# 468332_001_Step-Down_Controller.net
KiCad netlist of a schematic drawn in Altium Designer
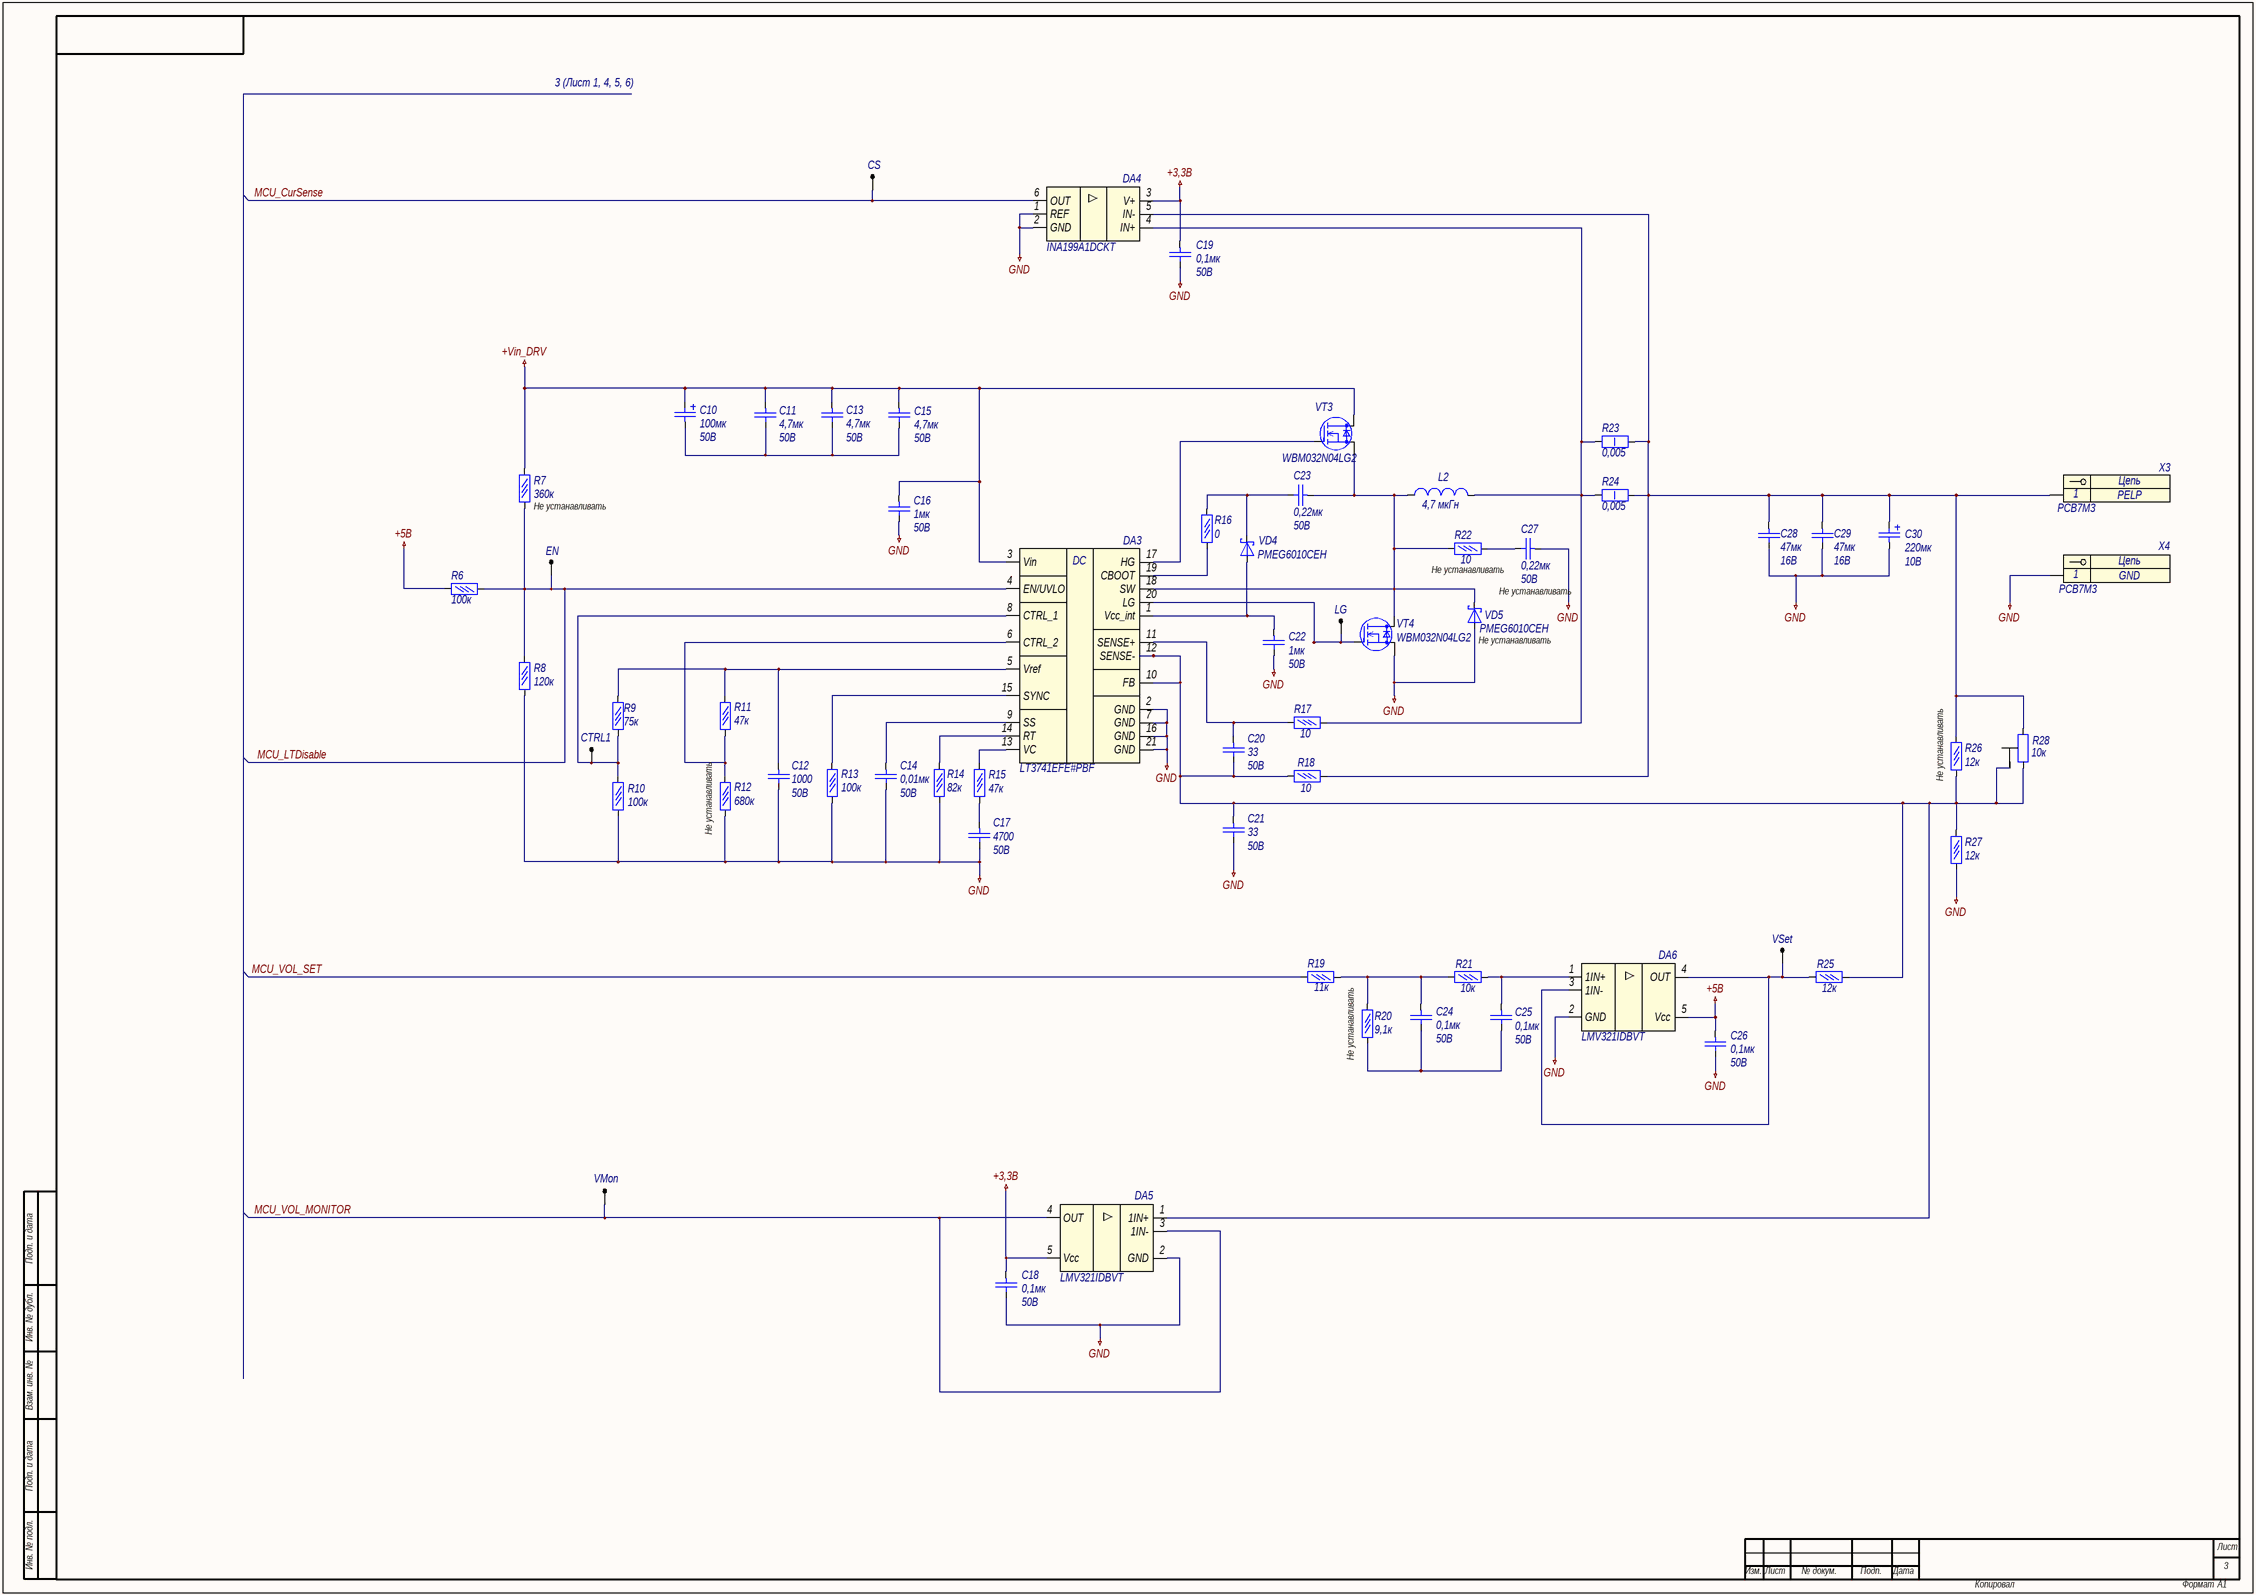
[diagram p0: РЕУН.468332.001_Step-Down_Controller.SchDoc]

(export (version "E")
  (design (tool "Eeschema 10.0.6"))
  (components
    (comp (ref "C10")
      (value "100мк")
      (footprint "C0805_AA")
      (description "Конденсатор пол.")
      (fields (field (name "VOLTAGE") "50В"))
      (libsource (lib "Library_Diana") (part "Конденсатор поляризованный"))
    )
    (comp (ref "C11")
      (value "4,7мк")
      (footprint "C0805_AA")
      (description "Конденсатор кер.")
      (fields (field (name "VOLTAGE") "50В"))
      (libsource (lib "Library_Diana") (part "Конденсатор кер."))
    )
    (comp (ref "C12")
      (value "1000")
      (footprint "C0805_AA")
      (description "Конденсатор кер.")
      (fields (field (name "VOLTAGE") "50В"))
      (libsource (lib "Library_Diana") (part "Конденсатор кер."))
    )
    (comp (ref "C13")
      (value "4,7мк")
      (footprint "C0805_AA")
      (description "Конденсатор кер.")
      (fields (field (name "VOLTAGE") "50В"))
      (libsource (lib "Library_Diana") (part "Конденсатор кер."))
    )
    (comp (ref "C14")
      (value "0,01мк")
      (footprint "C0805_AA")
      (description "Конденсатор кер.")
      (fields (field (name "VOLTAGE") "50В"))
      (libsource (lib "Library_Diana") (part "Конденсатор кер."))
    )
    (comp (ref "C15")
      (value "4,7мк")
      (footprint "C0805_AA")
      (description "Конденсатор кер.")
      (fields (field (name "VOLTAGE") "50В"))
      (libsource (lib "Library_Diana") (part "Конденсатор кер."))
    )
    (comp (ref "C16")
      (value "1мк")
      (footprint "C0805_AA")
      (description "Конденсатор кер.")
      (fields (field (name "VOLTAGE") "50В"))
      (libsource (lib "Library_Diana") (part "Конденсатор кер."))
    )
    (comp (ref "C17")
      (value "4700")
      (footprint "C0805_AA")
      (description "Конденсатор кер.")
      (fields (field (name "VOLTAGE") "50В"))
      (libsource (lib "Library_Diana") (part "Конденсатор кер."))
    )
    (comp (ref "C18")
      (value "0,1мк")
      (footprint "C0805_AA")
      (description "Конденсатор кер.")
      (fields (field (name "VOLTAGE") "50В"))
      (libsource (lib "Library_Diana") (part "Конденсатор кер."))
    )
    (comp (ref "C19")
      (value "0,1мк")
      (footprint "C0805_AA")
      (description "Конденсатор кер.")
      (fields (field (name "VOLTAGE") "50В"))
      (libsource (lib "Library_Diana") (part "Конденсатор кер."))
    )
    (comp (ref "C20")
      (value "33")
      (footprint "C0805_AA")
      (description "Конденсатор кер.")
      (fields (field (name "VOLTAGE") "50В"))
      (libsource (lib "Library_Diana") (part "Конденсатор кер."))
    )
    (comp (ref "C21")
      (value "33")
      (footprint "C0805_AA")
      (description "Конденсатор кер.")
      (fields (field (name "VOLTAGE") "50В"))
      (libsource (lib "Library_Diana") (part "Конденсатор кер."))
    )
    (comp (ref "C22")
      (value "1мк")
      (footprint "C0805_AA")
      (description "Конденсатор кер.")
      (fields (field (name "VOLTAGE") "50В"))
      (libsource (lib "Library_Diana") (part "Конденсатор кер."))
    )
    (comp (ref "C23")
      (value "0,22мк")
      (footprint "C0805_AA")
      (description "Конденсатор кер.")
      (fields (field (name "VOLTAGE") "50В"))
      (libsource (lib "Library_Diana") (part "Конденсатор кер."))
    )
    (comp (ref "C24")
      (value "0,1мк")
      (footprint "C0805_AA")
      (description "Конденсатор кер.")
      (fields (field (name "VOLTAGE") "50В"))
      (libsource (lib "Library_Diana") (part "Конденсатор кер."))
    )
    (comp (ref "C25")
      (value "0,1мк")
      (footprint "C0805_AA")
      (description "Конденсатор кер.")
      (fields (field (name "VOLTAGE") "50В"))
      (libsource (lib "Library_Diana") (part "Конденсатор кер."))
    )
    (comp (ref "C26")
      (value "0,1мк")
      (footprint "C0805_AA")
      (description "Конденсатор кер.")
      (fields (field (name "VOLTAGE") "50В"))
      (libsource (lib "Library_Diana") (part "Конденсатор кер."))
    )
    (comp (ref "C27")
      (value "0,22мк")
      (footprint "C0805_AA")
      (description "Конденсатор кер.")
      (fields (field (name "VOLTAGE") "50В"))
      (libsource (lib "Library_Diana") (part "Конденсатор кер."))
    )
    (comp (ref "C28")
      (value "47мк")
      (footprint "C0805_AA")
      (description "Конденсатор кер.")
      (fields (field (name "VOLTAGE") "16В"))
      (libsource (lib "Library_Diana") (part "Конденсатор кер."))
    )
    (comp (ref "C29")
      (value "47мк")
      (footprint "C0805_AA")
      (description "Конденсатор кер.")
      (fields (field (name "VOLTAGE") "16В"))
      (libsource (lib "Library_Diana") (part "Конденсатор кер."))
    )
    (comp (ref "C30")
      (value "220мк")
      (footprint "C0805_AA")
      (description "Конденсатор пол.")
      (fields (field (name "VOLTAGE") "10В"))
      (libsource (lib "Library_Diana") (part "Конденсатор поляризованный"))
    )
    (comp (ref "CS")
      (value "\"1\"")
      (footprint "0.5 x 1_round")
      (description "Test point")
      (libsource (lib "TarabusLib_KOR") (part "TestPoint"))
    )
    (comp (ref "CTRL1")
      (value "\"1\"")
      (footprint "0.5 x 1_round")
      (description "Test point")
      (libsource (lib "TarabusLib_KOR") (part "TestPoint"))
    )
    (comp (ref "DA3")
      (value "LT3741EFE#PBF")
      (description "Step-Down Controller, Constant Voltage")
      (libsource (lib "Library_Diana") (part "LT3741"))
    )
    (comp (ref "DA4")
      (value "INA199A1DCKT")
      (description "Voltage output current shunt monitor")
      (libsource (lib "Library_Diana") (part "INA199"))
    )
    (comp (ref "DA5")
      (value "LMV321IDBVT")
      (description "Операционный усилитель Rail-to-rail")
      (libsource (lib "") (part "LMV321_1"))
    )
    (comp (ref "DA6")
      (value "LMV321IDBVT")
      (description "Операционный усилитель Rail-to-rail")
      (libsource (lib "Library_Diana") (part "LMV321"))
    )
    (comp (ref "EN")
      (value "\"1\"")
      (footprint "0.5 x 1_round")
      (description "Test point")
      (libsource (lib "TarabusLib_KOR") (part "TestPoint"))
    )
    (comp (ref "L2")
      (value "4,7 мкГн")
      (footprint "L0603_A")
      (description "Катушка индуктивности")
      (libsource (lib "Library_Diana") (part "Inductor"))
    )
    (comp (ref "LG")
      (value "\"1\"")
      (footprint "0.5 x 1_round")
      (description "Test point")
      (libsource (lib "TarabusLib_KOR") (part "TestPoint"))
    )
    (comp (ref "R6")
      (value "100к")
      (footprint "R1206")
      (description "Резистор 0,05Вт")
      (libsource (lib "") (part "Резистор  0,05Вт_2"))
    )
    (comp (ref "R7")
      (value "360к")
      (footprint "R1206")
      (description "Резистор 0,05Вт")
      (libsource (lib "") (part "Резистор  0,05Вт_1"))
    )
    (comp (ref "R8")
      (value "120к")
      (footprint "R1206")
      (description "Резистор 0,05Вт")
      (libsource (lib "") (part "Резистор  0,05Вт_1"))
    )
    (comp (ref "R9")
      (value "75к")
      (footprint "R1206")
      (description "Резистор 0,05Вт")
      (libsource (lib "") (part "Резистор  0,05Вт_3"))
    )
    (comp (ref "R10")
      (value "100к")
      (footprint "R1206")
      (description "Резистор 0,05Вт")
      (libsource (lib "") (part "Резистор  0,05Вт_1"))
    )
    (comp (ref "R11")
      (value "47к")
      (footprint "R1206")
      (description "Резистор 0,05Вт")
      (libsource (lib "") (part "Резистор  0,05Вт_1"))
    )
    (comp (ref "R12")
      (value "680к")
      (footprint "R1206")
      (description "Резистор 0,05Вт")
      (libsource (lib "") (part "Резистор  0,05Вт_1"))
    )
    (comp (ref "R13")
      (value "100к")
      (footprint "R1206")
      (description "Резистор 0,05Вт")
      (libsource (lib "") (part "Резистор  0,05Вт_1"))
    )
    (comp (ref "R14")
      (value "82к")
      (footprint "R1206")
      (description "Резистор 0,05Вт")
      (libsource (lib "") (part "Резистор  0,05Вт_1"))
    )
    (comp (ref "R15")
      (value "47к")
      (footprint "R1206")
      (description "Резистор 0,05Вт")
      (libsource (lib "") (part "Резистор  0,05Вт_1"))
    )
    (comp (ref "R16")
      (value "0")
      (footprint "R1206")
      (description "Резистор 0,05Вт")
      (libsource (lib "") (part "Резистор  0,05Вт_1"))
    )
    (comp (ref "R17")
      (value "10")
      (footprint "R1206")
      (description "Резистор 0,05Вт")
      (libsource (lib "Library_Diana") (part "Резистор  0,05Вт"))
    )
    (comp (ref "R18")
      (value "10")
      (footprint "R1206")
      (description "Резистор 0,05Вт")
      (libsource (lib "Library_Diana") (part "Резистор  0,05Вт"))
    )
    (comp (ref "R19")
      (value "11к")
      (footprint "R1206")
      (description "Резистор 0,05Вт")
      (libsource (lib "") (part "Резистор  0,05Вт_2"))
    )
    (comp (ref "R20")
      (value "9,1к")
      (footprint "R1206")
      (description "Резистор 0,05Вт")
      (libsource (lib "") (part "Резистор  0,05Вт_1"))
    )
    (comp (ref "R21")
      (value "10к")
      (footprint "R1206")
      (description "Резистор 0,05Вт")
      (libsource (lib "") (part "Резистор  0,05Вт_2"))
    )
    (comp (ref "R22")
      (value "10")
      (footprint "R1206")
      (description "Резистор 0,05Вт")
      (libsource (lib "Library_Diana") (part "Резистор  0,05Вт"))
    )
    (comp (ref "R23")
      (value "0,005")
      (footprint "R1206")
      (description "Резистор  1Вт")
      (libsource (lib "Library_Diana") (part "Резистор  1Вт"))
    )
    (comp (ref "R24")
      (value "0,005")
      (footprint "R1206")
      (description "Резистор  1Вт")
      (libsource (lib "Library_Diana") (part "Резистор  1Вт"))
    )
    (comp (ref "R25")
      (value "12к")
      (footprint "R1206")
      (description "Резистор 0,05Вт")
      (libsource (lib "") (part "Резистор  0,05Вт_2"))
    )
    (comp (ref "R26")
      (value "12к")
      (footprint "R1206")
      (description "Резистор 0,05Вт")
      (libsource (lib "") (part "Резистор  0,05Вт_1"))
    )
    (comp (ref "R27")
      (value "12к")
      (footprint "R1206")
      (description "Резистор 0,05Вт")
      (libsource (lib "") (part "Резистор  0,05Вт_1"))
    )
    (comp (ref "R28")
      (value "10к")
      (description "Potentiometer")
      (libsource (lib "Library_Diana") (part "Potentiometer"))
    )
    (comp (ref "VD4")
      (value "PMEG6010CEH")
      (footprint "SOD123_A")
      (description "Диод Шоттки")
      (libsource (lib "Library_Diana") (part "DiodeSchottky"))
    )
    (comp (ref "VD5")
      (value "PMEG6010CEH")
      (footprint "SOD123_A")
      (description "Диод Шоттки")
      (libsource (lib "Library_Diana") (part "DiodeSchottky"))
    )
    (comp (ref "VMon")
      (value "\"1\"")
      (footprint "0.5 x 1_round")
      (description "Test point")
      (libsource (lib "TarabusLib_KOR") (part "TestPoint"))
    )
    (comp (ref "VSet")
      (value "\"1\"")
      (footprint "0.5 x 1_round")
      (description "Test point")
      (libsource (lib "TarabusLib_KOR") (part "TestPoint"))
    )
    (comp (ref "VT3")
      (value "WBM032N04LG2")
      (footprint "КТ-111В-1.02")
      (description "N-канальный транзистор")
      (fields (field (name "NAME") "WBM032N04LG2"))
      (libsource (lib "Library_Diana") (part "N-Mosfet"))
    )
    (comp (ref "VT4")
      (value "WBM032N04LG2")
      (footprint "КТ-111В-1.02")
      (description "N-канальный транзистор")
      (fields (field (name "NAME") "WBM032N04LG2"))
      (libsource (lib "Library_Diana") (part "N-Mosfet"))
    )
    (comp (ref "X3")
      (value "PCB7M3")
      (description "Разъем - 1 конт. клемма")
      (fields (field (name "NAME") "PCB7M3"))
      (libsource (lib "Library_Diana") (part "x1-k"))
    )
    (comp (ref "X4")
      (value "PCB7M3")
      (description "Разъем - 1 конт. клемма")
      (fields (field (name "NAME") "PCB7M3"))
      (libsource (lib "Library_Diana") (part "x1-k"))
    )
  )
  (nets
    (net (code "1") (name "+3,3В") (class "Default")
      (node (ref "C18") (pin "2") (pinfunction "2_2") (pintype "passive"))
      (node (ref "C19") (pin "2") (pinfunction "2_2") (pintype "passive"))
      (node (ref "DA4") (pin "3") (pinfunction "V+_3") (pintype "passive"))
      (node (ref "DA5") (pin "5") (pinfunction "Vcc_5") (pintype "passive"))
    )
    (net (code "2") (name "+5В") (class "Default")
      (node (ref "C26") (pin "2") (pinfunction "2_2") (pintype "passive"))
      (node (ref "DA6") (pin "5") (pinfunction "Vcc_5") (pintype "passive"))
      (node (ref "R6") (pin "2") (pinfunction "2_2") (pintype "passive"))
    )
    (net (code "3") (name "+Vin_DRV") (class "Default")
      (node (ref "C10") (pin "1") (pinfunction "1_1") (pintype "passive"))
      (node (ref "C11") (pin "2") (pinfunction "2_2") (pintype "passive"))
      (node (ref "C13") (pin "2") (pinfunction "2_2") (pintype "passive"))
      (node (ref "C15") (pin "2") (pinfunction "2_2") (pintype "passive"))
      (node (ref "C16") (pin "2") (pinfunction "2_2") (pintype "passive"))
      (node (ref "DA3") (pin "3") (pinfunction "Vin_3") (pintype "power_in"))
      (node (ref "R7") (pin "2") (pinfunction "2_2") (pintype "passive"))
      (node (ref "VT3") (pin "3") (pinfunction "D_3") (pintype "passive"))
    )
    (net (code "4") (name "/MCU_CurSense") (class "Default")
      (node (ref "CS") (pin "1") (pinfunction "1_1") (pintype "passive"))
      (node (ref "DA4") (pin "6") (pinfunction "OUT_6") (pintype "passive"))
    )
    (net (code "5") (name "/MCU_LTDisable") (class "Default")
      (node (ref "DA3") (pin "4") (pinfunction "EN/UVLO_4") (pintype "power_in"))
      (node (ref "EN") (pin "1") (pinfunction "1_1") (pintype "passive"))
      (node (ref "R6") (pin "1") (pinfunction "1_1") (pintype "passive"))
      (node (ref "R7") (pin "1") (pinfunction "1_1") (pintype "passive"))
      (node (ref "R8") (pin "2") (pinfunction "2_2") (pintype "passive"))
    )
    (net (code "6") (name "/MCU_VOL_MONITOR") (class "Default")
      (node (ref "DA5") (pin "3") (pinfunction "1IN-_3") (pintype "passive"))
      (node (ref "DA5") (pin "4") (pinfunction "OUT_4") (pintype "passive"))
      (node (ref "VMon") (pin "1") (pinfunction "1_1") (pintype "passive"))
    )
    (net (code "7") (name "/MCU_VOL_SET") (class "Default")
      (node (ref "R19") (pin "2") (pinfunction "2_2") (pintype "passive"))
    )
    (net (code "8") (name "GND") (class "Default")
      (node (ref "C12") (pin "1") (pinfunction "1_1") (pintype "passive"))
      (node (ref "C14") (pin "1") (pinfunction "1_1") (pintype "passive"))
      (node (ref "C16") (pin "1") (pinfunction "1_1") (pintype "passive"))
      (node (ref "C17") (pin "1") (pinfunction "1_1") (pintype "passive"))
      (node (ref "C18") (pin "1") (pinfunction "1_1") (pintype "passive"))
      (node (ref "C19") (pin "1") (pinfunction "1_1") (pintype "passive"))
      (node (ref "C21") (pin "1") (pinfunction "1_1") (pintype "passive"))
      (node (ref "C22") (pin "1") (pinfunction "1_1") (pintype "passive"))
      (node (ref "C26") (pin "1") (pinfunction "1_1") (pintype "passive"))
      (node (ref "C27") (pin "2") (pinfunction "2_2") (pintype "passive"))
      (node (ref "C28") (pin "1") (pinfunction "1_1") (pintype "passive"))
      (node (ref "C29") (pin "1") (pinfunction "1_1") (pintype "passive"))
      (node (ref "C30") (pin "2") (pinfunction "2_2") (pintype "passive"))
      (node (ref "DA3") (pin "16") (pinfunction "GND_16") (pintype "power_in"))
      (node (ref "DA3") (pin "2") (pinfunction "GND_2") (pintype "power_in"))
      (node (ref "DA3") (pin "21") (pinfunction "GND_21") (pintype "power_in"))
      (node (ref "DA3") (pin "7") (pinfunction "GND_7") (pintype "power_in"))
      (node (ref "DA4") (pin "1") (pinfunction "REF_1") (pintype "passive"))
      (node (ref "DA4") (pin "2") (pinfunction "GND_2") (pintype "passive"))
      (node (ref "DA5") (pin "2") (pinfunction "GND_2") (pintype "passive"))
      (node (ref "DA6") (pin "2") (pinfunction "GND_2") (pintype "passive"))
      (node (ref "R10") (pin "1") (pinfunction "1_1") (pintype "passive"))
      (node (ref "R12") (pin "1") (pinfunction "1_1") (pintype "passive"))
      (node (ref "R13") (pin "1") (pinfunction "1_1") (pintype "passive"))
      (node (ref "R14") (pin "1") (pinfunction "1_1") (pintype "passive"))
      (node (ref "R27") (pin "1") (pinfunction "1_1") (pintype "passive"))
      (node (ref "R8") (pin "1") (pinfunction "1_1") (pintype "passive"))
      (node (ref "VD5") (pin "2") (pinfunction "A_2") (pintype "passive"))
      (node (ref "VT4") (pin "2") (pinfunction "S_2") (pintype "passive"))
      (node (ref "X4") (pin "1") (pinfunction "1_1") (pintype "passive"))
    )
    (net (code "9") (name "Net-(C10-Pad2)") (class "Default")
      (node (ref "C10") (pin "2") (pinfunction "2_2") (pintype "passive"))
      (node (ref "C11") (pin "1") (pinfunction "1_1") (pintype "passive"))
      (node (ref "C13") (pin "1") (pinfunction "1_1") (pintype "passive"))
      (node (ref "C15") (pin "1") (pinfunction "1_1") (pintype "passive"))
    )
    (net (code "10") (name "Net-(C17-Pad2)") (class "Default")
      (node (ref "C17") (pin "2") (pinfunction "2_2") (pintype "passive"))
      (node (ref "R15") (pin "1") (pinfunction "1_1") (pintype "passive"))
    )
    (net (code "11") (name "Net-(C24-Pad1)") (class "Default")
      (node (ref "C24") (pin "1") (pinfunction "1_1") (pintype "passive"))
      (node (ref "C25") (pin "1") (pinfunction "1_1") (pintype "passive"))
      (node (ref "R20") (pin "1") (pinfunction "1_1") (pintype "passive"))
    )
    (net (code "12") (name "Net-(C24-Pad2)") (class "Default")
      (node (ref "C24") (pin "2") (pinfunction "2_2") (pintype "passive"))
      (node (ref "R19") (pin "1") (pinfunction "1_1") (pintype "passive"))
      (node (ref "R20") (pin "2") (pinfunction "2_2") (pintype "passive"))
      (node (ref "R21") (pin "2") (pinfunction "2_2") (pintype "passive"))
    )
    (net (code "13") (name "Net-(C27-Pad1)") (class "Default")
      (node (ref "C27") (pin "1") (pinfunction "1_1") (pintype "passive"))
      (node (ref "R22") (pin "2") (pinfunction "2_2") (pintype "passive"))
    )
    (net (code "14") (name "Net-(DA3-CBOOT)") (class "Default")
      (node (ref "DA3") (pin "19") (pinfunction "CBOOT_19") (pintype "power_in"))
      (node (ref "R16") (pin "1") (pinfunction "1_1") (pintype "passive"))
    )
    (net (code "15") (name "Net-(DA3-CTRL_1)") (class "Default")
      (node (ref "CTRL1") (pin "1") (pinfunction "1_1") (pintype "passive"))
      (node (ref "DA3") (pin "8") (pinfunction "CTRL_1_8") (pintype "power_in"))
      (node (ref "R10") (pin "2") (pinfunction "2_2") (pintype "passive"))
      (node (ref "R9") (pin "2") (pinfunction "2_2") (pintype "passive"))
    )
    (net (code "16") (name "Net-(DA3-CTRL_2)") (class "Default")
      (node (ref "DA3") (pin "6") (pinfunction "CTRL_2_6") (pintype "power_in"))
      (node (ref "R11") (pin "1") (pinfunction "1_1") (pintype "passive"))
      (node (ref "R12") (pin "2") (pinfunction "2_2") (pintype "passive"))
    )
    (net (code "17") (name "Net-(DA3-FB)") (class "Default")
      (node (ref "C20") (pin "1") (pinfunction "1_1") (pintype "passive"))
      (node (ref "C21") (pin "2") (pinfunction "2_2") (pintype "passive"))
      (node (ref "DA3") (pin "10") (pinfunction "FB_10") (pintype "power_in"))
      (node (ref "DA3") (pin "12") (pinfunction "SENSE-_12") (pintype "power_in"))
      (node (ref "DA5") (pin "1") (pinfunction "1IN+_1") (pintype "passive"))
      (node (ref "R18") (pin "1") (pinfunction "1_1") (pintype "passive"))
      (node (ref "R25") (pin "1") (pinfunction "1_1") (pintype "passive"))
      (node (ref "R26") (pin "1") (pinfunction "1_1") (pintype "passive"))
      (node (ref "R27") (pin "2") (pinfunction "2_2") (pintype "passive"))
      (node (ref "R28") (pin "2") (pinfunction "2_2") (pintype "passive"))
      (node (ref "R28") (pin "3") (pinfunction "3_3") (pintype "passive"))
    )
    (net (code "18") (name "Net-(DA3-HG)") (class "Default")
      (node (ref "DA3") (pin "17") (pinfunction "HG_17") (pintype "power_in"))
      (node (ref "VT3") (pin "1") (pinfunction "G_1") (pintype "passive"))
    )
    (net (code "19") (name "Net-(DA3-LG)") (class "Default")
      (node (ref "DA3") (pin "20") (pinfunction "LG_20") (pintype "power_in"))
      (node (ref "LG") (pin "1") (pinfunction "1_1") (pintype "passive"))
      (node (ref "VT4") (pin "1") (pinfunction "G_1") (pintype "passive"))
    )
    (net (code "20") (name "Net-(DA3-RT)") (class "Default")
      (node (ref "DA3") (pin "14") (pinfunction "RT_14") (pintype "power_in"))
      (node (ref "R14") (pin "2") (pinfunction "2_2") (pintype "passive"))
    )
    (net (code "21") (name "Net-(DA3-SENSE+)") (class "Default")
      (node (ref "C20") (pin "2") (pinfunction "2_2") (pintype "passive"))
      (node (ref "DA3") (pin "11") (pinfunction "SENSE+_11") (pintype "power_in"))
      (node (ref "R17") (pin "1") (pinfunction "1_1") (pintype "passive"))
    )
    (net (code "22") (name "Net-(DA3-SS)") (class "Default")
      (node (ref "C14") (pin "2") (pinfunction "2_2") (pintype "passive"))
      (node (ref "DA3") (pin "9") (pinfunction "SS_9") (pintype "power_in"))
    )
    (net (code "23") (name "Net-(DA3-SW)") (class "Default")
      (node (ref "C23") (pin "2") (pinfunction "2_2") (pintype "passive"))
      (node (ref "DA3") (pin "18") (pinfunction "SW_18") (pintype "power_in"))
      (node (ref "L2") (pin "1") (pinfunction "1_1") (pintype "passive"))
      (node (ref "R22") (pin "1") (pinfunction "1_1") (pintype "passive"))
      (node (ref "VD5") (pin "1") (pinfunction "K_1") (pintype "passive"))
      (node (ref "VT3") (pin "2") (pinfunction "S_2") (pintype "passive"))
      (node (ref "VT4") (pin "3") (pinfunction "D_3") (pintype "passive"))
    )
    (net (code "24") (name "Net-(DA3-SYNC)") (class "Default")
      (node (ref "DA3") (pin "15") (pinfunction "SYNC_15") (pintype "power_in"))
      (node (ref "R13") (pin "2") (pinfunction "2_2") (pintype "passive"))
    )
    (net (code "25") (name "Net-(DA3-VC)") (class "Default")
      (node (ref "DA3") (pin "13") (pinfunction "VC_13") (pintype "power_in"))
      (node (ref "R15") (pin "2") (pinfunction "2_2") (pintype "passive"))
    )
    (net (code "26") (name "Net-(DA3-Vcc_int)") (class "Default")
      (node (ref "C22") (pin "2") (pinfunction "2_2") (pintype "passive"))
      (node (ref "DA3") (pin "1") (pinfunction "Vcc_int_1") (pintype "power_in"))
      (node (ref "VD4") (pin "2") (pinfunction "A_2") (pintype "passive"))
    )
    (net (code "27") (name "Net-(DA3-Vref)") (class "Default")
      (node (ref "C12") (pin "2") (pinfunction "2_2") (pintype "passive"))
      (node (ref "DA3") (pin "5") (pinfunction "Vref_5") (pintype "power_in"))
      (node (ref "R11") (pin "2") (pinfunction "2_2") (pintype "passive"))
      (node (ref "R9") (pin "1") (pinfunction "1_1") (pintype "passive"))
    )
    (net (code "28") (name "Net-(DA4-IN+)") (class "Default")
      (node (ref "DA4") (pin "4") (pinfunction "IN+_4") (pintype "passive"))
      (node (ref "L2") (pin "2") (pinfunction "2_2") (pintype "passive"))
      (node (ref "R17") (pin "2") (pinfunction "2_2") (pintype "passive"))
      (node (ref "R23") (pin "1") (pinfunction "1_1") (pintype "passive"))
      (node (ref "R24") (pin "1") (pinfunction "1_1") (pintype "passive"))
    )
    (net (code "29") (name "Net-(DA4-IN-)") (class "Default")
      (node (ref "C28") (pin "2") (pinfunction "2_2") (pintype "passive"))
      (node (ref "C29") (pin "2") (pinfunction "2_2") (pintype "passive"))
      (node (ref "C30") (pin "1") (pinfunction "1_1") (pintype "passive"))
      (node (ref "DA4") (pin "5") (pinfunction "IN-_5") (pintype "passive"))
      (node (ref "R18") (pin "2") (pinfunction "2_2") (pintype "passive"))
      (node (ref "R23") (pin "2") (pinfunction "2_2") (pintype "passive"))
      (node (ref "R24") (pin "2") (pinfunction "2_2") (pintype "passive"))
      (node (ref "R26") (pin "2") (pinfunction "2_2") (pintype "passive"))
      (node (ref "R28") (pin "1") (pinfunction "1_1") (pintype "passive"))
      (node (ref "X3") (pin "1") (pinfunction "1_1") (pintype "passive"))
    )
    (net (code "30") (name "Net-(DA6-1IN+)") (class "Default")
      (node (ref "C25") (pin "2") (pinfunction "2_2") (pintype "passive"))
      (node (ref "DA6") (pin "1") (pinfunction "1IN+_1") (pintype "passive"))
      (node (ref "R21") (pin "1") (pinfunction "1_1") (pintype "passive"))
    )
    (net (code "31") (name "Net-(DA6-1IN-)") (class "Default")
      (node (ref "DA6") (pin "3") (pinfunction "1IN-_3") (pintype "passive"))
      (node (ref "DA6") (pin "4") (pinfunction "OUT_4") (pintype "passive"))
      (node (ref "R25") (pin "2") (pinfunction "2_2") (pintype "passive"))
      (node (ref "VSet") (pin "1") (pinfunction "1_1") (pintype "passive"))
    )
    (net (code "32") (name "Net-(VD4-K)") (class "Default")
      (node (ref "C23") (pin "1") (pinfunction "1_1") (pintype "passive"))
      (node (ref "R16") (pin "2") (pinfunction "2_2") (pintype "passive"))
      (node (ref "VD4") (pin "1") (pinfunction "K_1") (pintype "passive"))
    )
  )
)
